# Ubo_side_v1_4.net
KiCad netlist of a schematic drawn in EAGLE
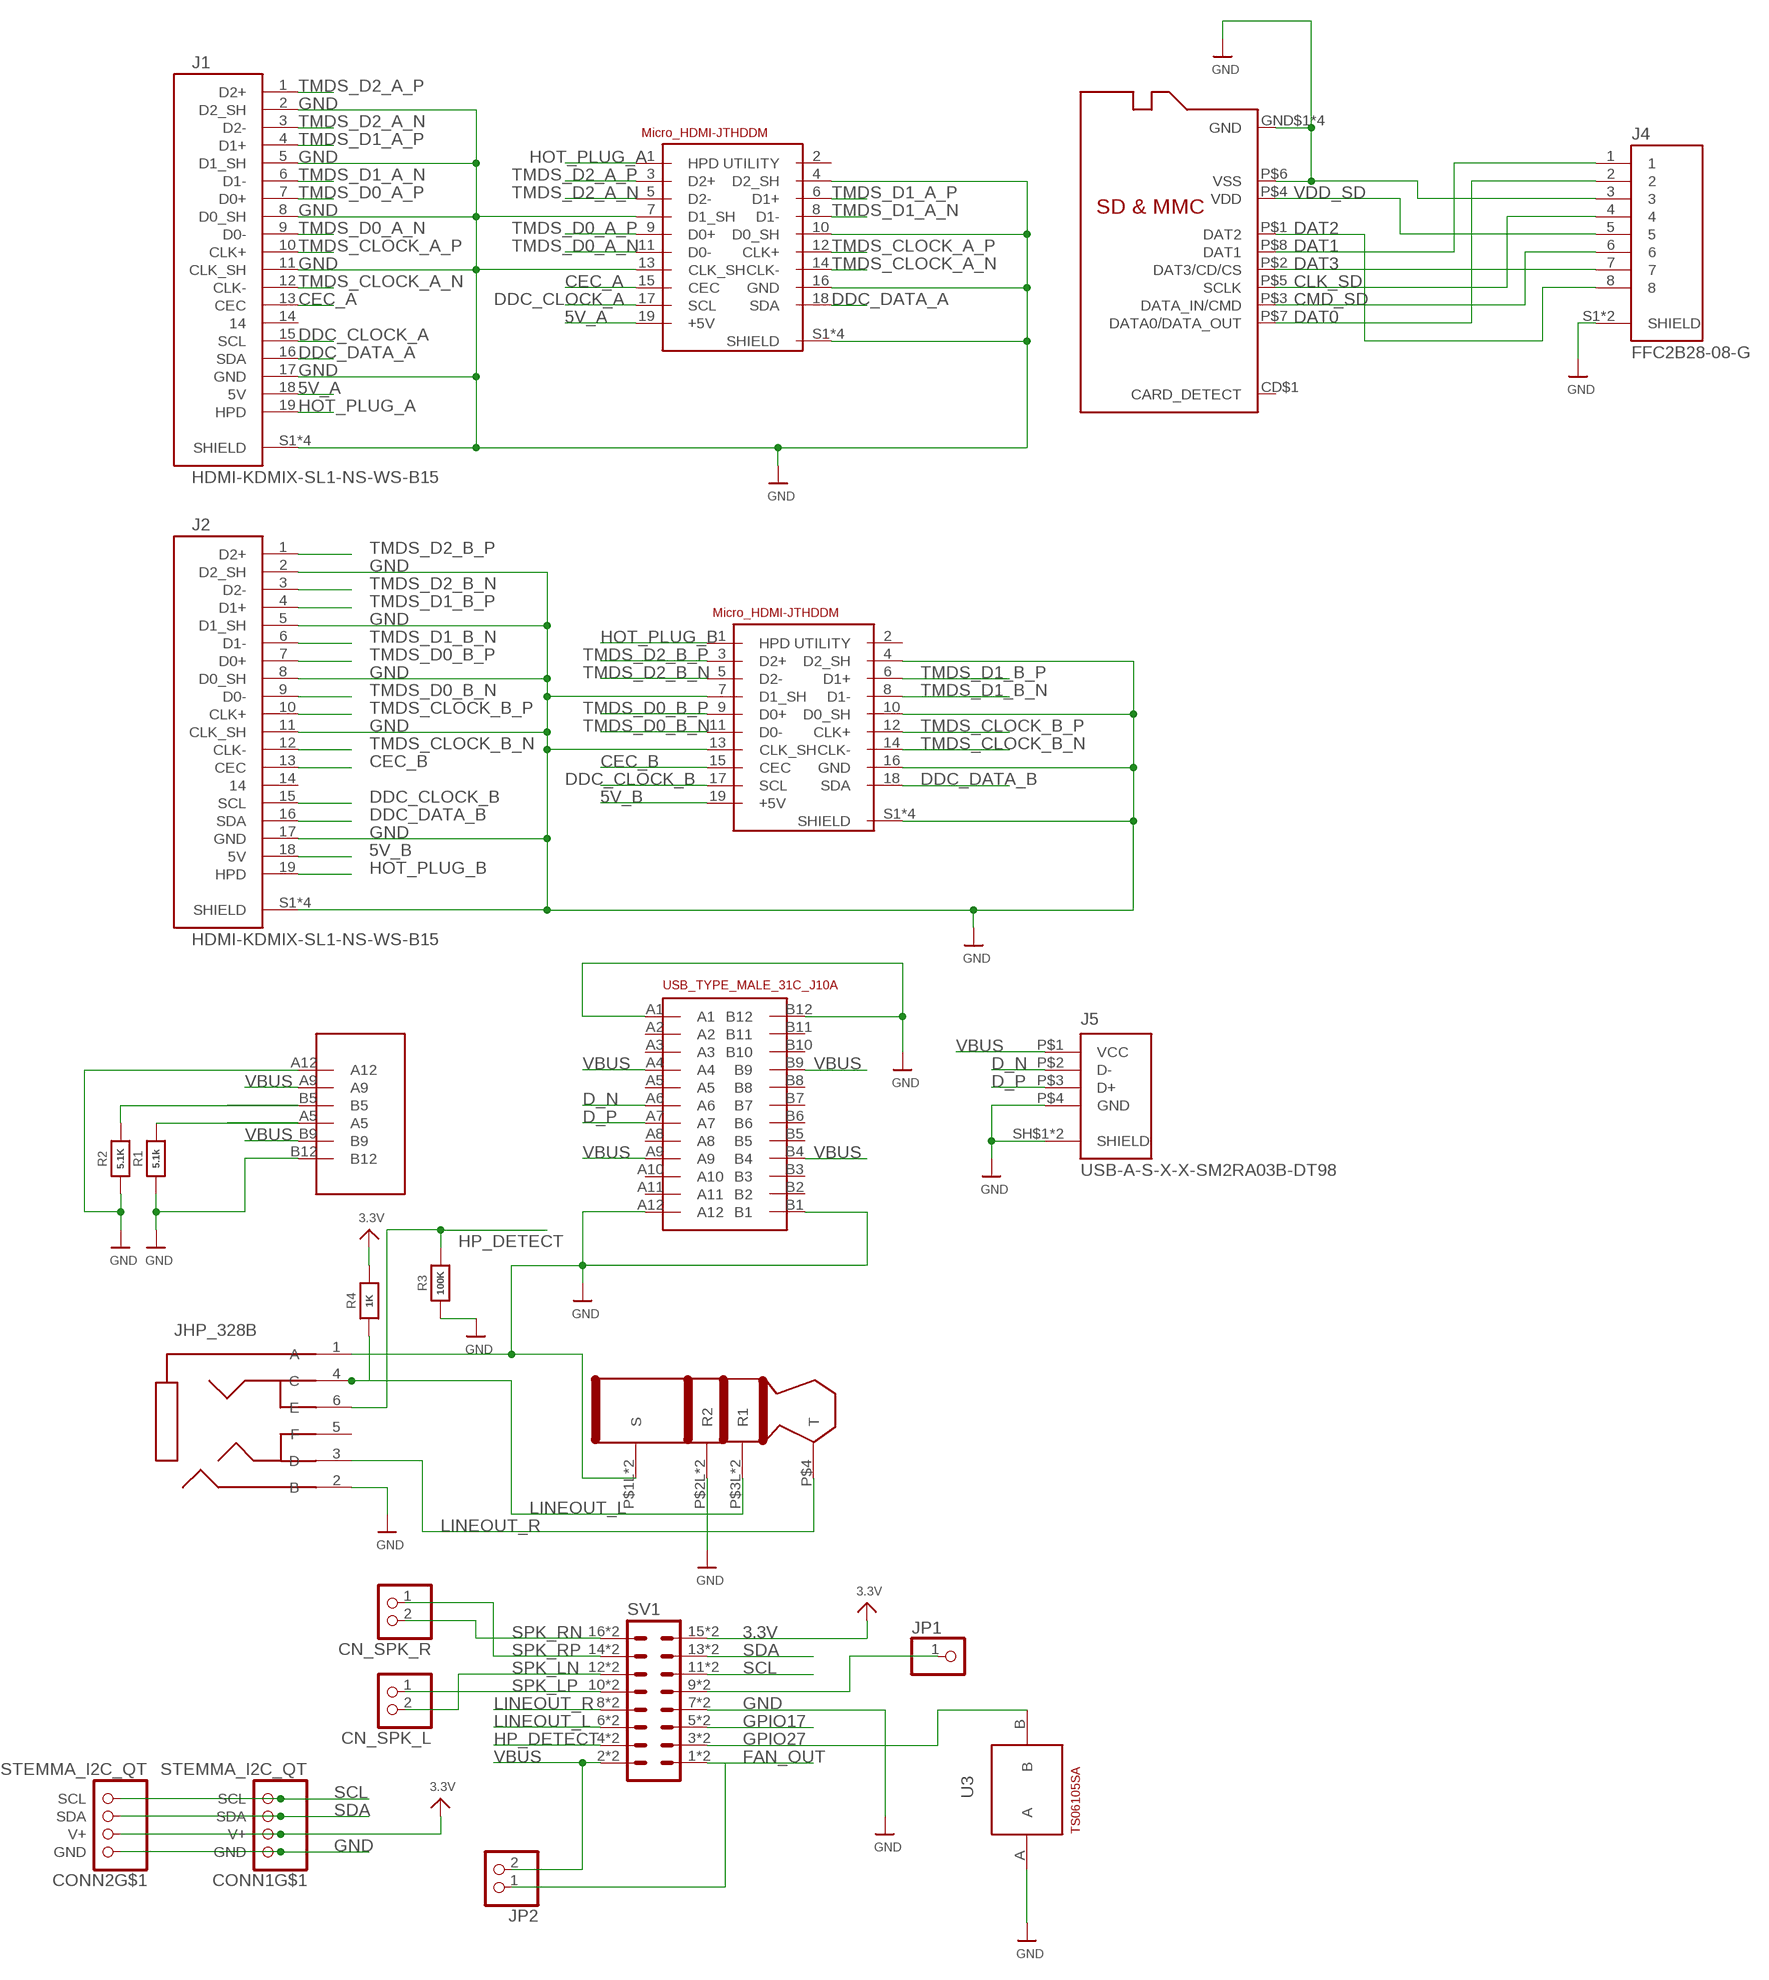
[diagram p0: schematic, sheet 1]

(export (version "E")
  (design (tool "Eeschema 10.0.6"))
  (components
    (comp (ref "AUD_CON")
      (value "AUDIO_3.5MMJACK_MALE")
      (footprint "eagle-import:AUDIO_3.5MM_JACK_MALE")
      (libsource (lib "eagle-import") (part "AUDIO_3.5MMJACK_MALE"))
    )
    (comp (ref "CN_SPK_L")
      (value "JST_2PIN-SMT")
      (footprint "eagle-import:JST-PH-2-SMT")
      (libsource (lib "eagle-import") (part "JST_2PIN-SMT"))
    )
    (comp (ref "CN_SPK_R")
      (value "JST_2PIN-SMT")
      (footprint "eagle-import:JST-PH-2-SMT")
      (libsource (lib "eagle-import") (part "JST_2PIN-SMT"))
    )
    (comp (ref "CONN1")
      (value "STEMMA_I2C_QT")
      (footprint "eagle-import:JST_SH4")
      (libsource (lib "eagle-import") (part "STEMMA_I2C_QT"))
    )
    (comp (ref "CONN2")
      (value "STEMMA_I2C_QT")
      (footprint "eagle-import:JST_SH4")
      (libsource (lib "eagle-import") (part "STEMMA_I2C_QT"))
    )
    (comp (ref "J1")
      (value "HDMI-KDMIX-SL1-NS-WS-B15")
      (footprint "eagle-import:CONN_KDMIX-SL1-NS-WS-B15")
      (fields
        (field (name "DIGI-KEY_PART_NUMBER") "2092-KDMIX-SL1-NS-WS-B15-ND")
        (field (name "MF") "Kycon")
        (field (name "MP") "KDMIX-SL1-NS-WS-B15")
      )
      (libsource (lib "eagle-import") (part "HDMI-KDMIX-SL1-NS-WS-B15"))
    )
    (comp (ref "J2")
      (value "HDMI-KDMIX-SL1-NS-WS-B15")
      (footprint "eagle-import:CONN_KDMIX-SL1-NS-WS-B15")
      (fields
        (field (name "DIGI-KEY_PART_NUMBER") "2092-KDMIX-SL1-NS-WS-B15-ND")
        (field (name "MF") "Kycon")
        (field (name "MP") "KDMIX-SL1-NS-WS-B15")
      )
      (libsource (lib "eagle-import") (part "HDMI-KDMIX-SL1-NS-WS-B15"))
    )
    (comp (ref "J4")
      (value "FFC2B28-08-G")
      (footprint "eagle-import:GCT_FFC2B28-08-G")
      (fields (field (name "MF") "Global Connector Technology"))
      (libsource (lib "eagle-import") (part "FFC2B28-08-G"))
    )
    (comp (ref "J5")
      (value "USB-A-S-X-X-SM2RA03B-DT98")
      (footprint "eagle-import:USB-A-RA03B-DT98")
      (libsource (lib "eagle-import") (part "USB-A-S-X-X-SM2RA03B-DT98"))
    )
    (comp (ref "JP1")
      (value "PINHD-1X1")
      (footprint "eagle-import:1X01")
      (libsource (lib "eagle-import") (part "PINHD-1X1"))
    )
    (comp (ref "JP2")
      (value "PINHD-1X2/90")
      (footprint "eagle-import:1X02_90")
      (libsource (lib "eagle-import") (part "PINHD-1X2/90"))
    )
    (comp (ref "MICROHDMI1")
      (value "MICRO_HDMI_JTHDDM")
      (footprint "eagle-import:MICRO_HDMI_JTHDDM")
      (fields (field (name "MF") "MTCONN ELECTRONICS CO.,LTD") (field (name "MPN") "JTHDDM_0200D1SP79"))
      (libsource (lib "eagle-import") (part "MICRO_HDMI_JTHDDM"))
    )
    (comp (ref "MICROHDMI2")
      (value "MICRO_HDMI_JTHDDM")
      (footprint "eagle-import:MICRO_HDMI_JTHDDM")
      (fields (field (name "MF") "MTCONN ELECTRONICS CO.,LTD") (field (name "MPN") "JTHDDM_0200D1SP79"))
      (libsource (lib "eagle-import") (part "MICRO_HDMI_JTHDDM"))
    )
    (comp (ref "R1")
      (value "5.1k")
      (footprint "eagle-import:_0603")
      (libsource (lib "eagle-import") (part "RESISTOR_0603"))
    )
    (comp (ref "R2")
      (value "5.1K")
      (footprint "eagle-import:_0603")
      (libsource (lib "eagle-import") (part "RESISTOR_0603"))
    )
    (comp (ref "R3")
      (value "100K")
      (footprint "eagle-import:_0603")
      (libsource (lib "eagle-import") (part "RESISTOR_0603"))
    )
    (comp (ref "R4")
      (value "1K")
      (footprint "eagle-import:_0603")
      (libsource (lib "eagle-import") (part "RESISTOR_0603"))
    )
    (comp (ref "SV1")
      (value "MA08X2-FEMALE")
      (footprint "eagle-import:MA08X2-FEMALE")
      (libsource (lib "eagle-import") (part "MA08X2-FEMALE"))
    )
    (comp (ref "U1")
      (value "AUDIO_SOCKET_JHP_328BPJ-3160")
      (footprint "eagle-import:PJ-3160")
      (libsource (lib "eagle-import") (part "AUDIO_SOCKET_JHP_328BPJ-3160"))
    )
    (comp (ref "U2")
      (value "USB-20C-F-06CD-1")
      (footprint "eagle-import:USB_20C_F_60CD")
      (libsource (lib "eagle-import") (part "USB-20C-F-06CD-1"))
    )
    (comp (ref "U3")
      (value "TS06105SA")
      (footprint "eagle-import:TS-06105SA-1")
      (libsource (lib "eagle-import") (part "TS06105SA"))
    )
    (comp (ref "U4")
      (value "MICROSDTF01-H1.8")
      (footprint "eagle-import:MICROSDTF-01-H1.8")
      (libsource (lib "eagle-import") (part "MICROSDTF01-H1.8"))
    )
    (comp (ref "USBC")
      (value "USB_TYPE_MALE_31C_J10C")
      (footprint "eagle-import:USB_TYPE_MALE_31C_J10A")
      (fields (field (name "MF") "XIAMEN JINBEILI ELECTRONICS CO.,LTD") (field (name "MPN") "USB_31C_M_J10A"))
      (libsource (lib "eagle-import") (part "USB_TYPE_MALE_31C_J10C"))
    )
  )
  (nets
    (net (code "1") (name "/5V_A") (class "Default")
      (node (ref "J1") (pin "18") (pinfunction "5V_18") (pintype "passive"))
      (node (ref "MICROHDMI1") (pin "19") (pinfunction "+5V_19") (pintype "bidirectional"))
    )
    (net (code "2") (name "/5V_B") (class "Default")
      (node (ref "J2") (pin "18") (pinfunction "5V_18") (pintype "passive"))
      (node (ref "MICROHDMI2") (pin "19") (pinfunction "+5V_19") (pintype "bidirectional"))
    )
    (net (code "3") (name "/CEC_A") (class "Default")
      (node (ref "J1") (pin "13") (pinfunction "CEC_13") (pintype "passive"))
      (node (ref "MICROHDMI1") (pin "15") (pinfunction "CEC_15") (pintype "bidirectional"))
    )
    (net (code "4") (name "/CEC_B") (class "Default")
      (node (ref "J2") (pin "13") (pinfunction "CEC_13") (pintype "passive"))
      (node (ref "MICROHDMI2") (pin "15") (pinfunction "CEC_15") (pintype "bidirectional"))
    )
    (net (code "5") (name "/CLK_SD") (class "Default")
      (node (ref "J4") (pin "4") (pinfunction "4_4") (pintype "passive"))
      (node (ref "U4") (pin "P$5") (pinfunction "SCLK_P$5") (pintype "input"))
    )
    (net (code "6") (name "/CMD_SD") (class "Default")
      (node (ref "J4") (pin "6") (pinfunction "6_6") (pintype "passive"))
      (node (ref "U4") (pin "P$3") (pinfunction "DATA_IN/CMD_P$3") (pintype "input"))
    )
    (net (code "7") (name "/DAT0") (class "Default")
      (node (ref "J4") (pin "2") (pinfunction "2_2") (pintype "passive"))
      (node (ref "U4") (pin "P$7") (pinfunction "DATA0/DATA_OUT_P$7") (pintype "output"))
    )
    (net (code "8") (name "/DAT1") (class "Default")
      (node (ref "J4") (pin "1") (pinfunction "1_1") (pintype "passive"))
      (node (ref "U4") (pin "P$8") (pinfunction "DAT1_P$8") (pintype "bidirectional"))
    )
    (net (code "9") (name "/DAT2") (class "Default")
      (node (ref "J4") (pin "8") (pinfunction "8_8") (pintype "passive"))
      (node (ref "U4") (pin "P$1") (pinfunction "DAT2_P$1") (pintype "bidirectional"))
    )
    (net (code "10") (name "/DAT3") (class "Default")
      (node (ref "J4") (pin "7") (pinfunction "7_7") (pintype "passive"))
      (node (ref "U4") (pin "P$2") (pinfunction "DAT3/CD/CS_P$2") (pintype "input"))
    )
    (net (code "11") (name "/DDC_CLOCK_A") (class "Default")
      (node (ref "J1") (pin "15") (pinfunction "SCL_15") (pintype "passive"))
      (node (ref "MICROHDMI1") (pin "17") (pinfunction "SCL_17") (pintype "bidirectional"))
    )
    (net (code "12") (name "/DDC_CLOCK_B") (class "Default")
      (node (ref "J2") (pin "15") (pinfunction "SCL_15") (pintype "passive"))
      (node (ref "MICROHDMI2") (pin "17") (pinfunction "SCL_17") (pintype "bidirectional"))
    )
    (net (code "13") (name "/DDC_DATA_A") (class "Default")
      (node (ref "J1") (pin "16") (pinfunction "SDA_16") (pintype "passive"))
      (node (ref "MICROHDMI1") (pin "18") (pinfunction "SDA_18") (pintype "bidirectional"))
    )
    (net (code "14") (name "/DDC_DATA_B") (class "Default")
      (node (ref "J2") (pin "16") (pinfunction "SDA_16") (pintype "passive"))
      (node (ref "MICROHDMI2") (pin "18") (pinfunction "SDA_18") (pintype "bidirectional"))
    )
    (net (code "15") (name "/D_N") (class "Default")
      (node (ref "J5") (pin "P$2") (pinfunction "D-_P$2") (pintype "bidirectional"))
      (node (ref "USBC") (pin "A6") (pinfunction "A6_A6") (pintype "bidirectional"))
    )
    (net (code "16") (name "/D_P") (class "Default")
      (node (ref "J5") (pin "P$3") (pinfunction "D+_P$3") (pintype "bidirectional"))
      (node (ref "USBC") (pin "A7") (pinfunction "A7_A7") (pintype "bidirectional"))
    )
    (net (code "17") (name "/FAN_OUT") (class "Default")
      (node (ref "JP2") (pin "1") (pinfunction "1_1") (pintype "passive"))
      (node (ref "SV1") (pin "1") (pinfunction "1_1") (pintype "passive"))
      (node (ref "SV1") (pin "P$1") (pinfunction "1_P$1") (pintype "passive"))
    )
    (net (code "18") (name "/GPIO17") (class "Default")
      (node (ref "SV1") (pin "5") (pinfunction "5_5") (pintype "passive"))
      (node (ref "SV1") (pin "P$5") (pinfunction "5_P$5") (pintype "passive"))
    )
    (net (code "19") (name "/GPIO27") (class "Default")
      (node (ref "SV1") (pin "3") (pinfunction "3_3") (pintype "passive"))
      (node (ref "SV1") (pin "P$3") (pinfunction "3_P$3") (pintype "passive"))
      (node (ref "U3") (pin "B") (pinfunction "B_B") (pintype "bidirectional"))
    )
    (net (code "20") (name "/HOT_PLUG_A") (class "Default")
      (node (ref "J1") (pin "19") (pinfunction "HPD_19") (pintype "passive"))
      (node (ref "MICROHDMI1") (pin "1") (pinfunction "HPD_1") (pintype "bidirectional"))
    )
    (net (code "21") (name "/HOT_PLUG_B") (class "Default")
      (node (ref "J2") (pin "19") (pinfunction "HPD_19") (pintype "passive"))
      (node (ref "MICROHDMI2") (pin "1") (pinfunction "HPD_1") (pintype "bidirectional"))
    )
    (net (code "22") (name "/HP_DETECT") (class "Default")
      (node (ref "R3") (pin "2") (pinfunction "2_2") (pintype "passive"))
      (node (ref "SV1") (pin "4") (pinfunction "4_4") (pintype "passive"))
      (node (ref "SV1") (pin "P$4") (pinfunction "4_P$4") (pintype "passive"))
      (node (ref "U1") (pin "6") (pinfunction "E_6") (pintype "bidirectional"))
    )
    (net (code "23") (name "/LINEOUT_L") (class "Default")
      (node (ref "AUD_CON") (pin "P$3L") (pinfunction "R1_P$3L") (pintype "bidirectional"))
      (node (ref "AUD_CON") (pin "P$3R") (pinfunction "R1_P$3R") (pintype "bidirectional"))
      (node (ref "R4") (pin "1") (pinfunction "1_1") (pintype "passive"))
      (node (ref "SV1") (pin "6") (pinfunction "6_6") (pintype "passive"))
      (node (ref "SV1") (pin "P$6") (pinfunction "6_P$6") (pintype "passive"))
      (node (ref "U1") (pin "4") (pinfunction "C_4") (pintype "bidirectional"))
    )
    (net (code "24") (name "/LINEOUT_R") (class "Default")
      (node (ref "AUD_CON") (pin "P$4") (pinfunction "T_P$4") (pintype "bidirectional"))
      (node (ref "SV1") (pin "8") (pinfunction "8_8") (pintype "passive"))
      (node (ref "SV1") (pin "P$8") (pinfunction "8_P$8") (pintype "passive"))
      (node (ref "U1") (pin "3") (pinfunction "D_3") (pintype "bidirectional"))
    )
    (net (code "25") (name "/SCL") (class "Default")
      (node (ref "CONN1") (pin "4") (pinfunction "SCL_4") (pintype "passive"))
      (node (ref "CONN2") (pin "4") (pinfunction "SCL_4") (pintype "passive"))
      (node (ref "SV1") (pin "11") (pinfunction "11_11") (pintype "passive"))
      (node (ref "SV1") (pin "P$11") (pinfunction "11_P$11") (pintype "passive"))
    )
    (net (code "26") (name "/SDA") (class "Default")
      (node (ref "CONN1") (pin "3") (pinfunction "SDA_3") (pintype "passive"))
      (node (ref "CONN2") (pin "3") (pinfunction "SDA_3") (pintype "passive"))
      (node (ref "SV1") (pin "13") (pinfunction "13_13") (pintype "passive"))
      (node (ref "SV1") (pin "P$13") (pinfunction "13_P$13") (pintype "passive"))
    )
    (net (code "27") (name "/SPK_LN") (class "Default")
      (node (ref "CN_SPK_L") (pin "2") (pinfunction "1_2") (pintype "passive"))
      (node (ref "SV1") (pin "12") (pinfunction "12_12") (pintype "passive"))
      (node (ref "SV1") (pin "P$12") (pinfunction "12_P$12") (pintype "passive"))
    )
    (net (code "28") (name "/SPK_LP") (class "Default")
      (node (ref "CN_SPK_L") (pin "1") (pinfunction "2_1") (pintype "passive"))
      (node (ref "SV1") (pin "10") (pinfunction "10_10") (pintype "passive"))
      (node (ref "SV1") (pin "P$10") (pinfunction "10_P$10") (pintype "passive"))
    )
    (net (code "29") (name "/SPK_RN") (class "Default")
      (node (ref "CN_SPK_R") (pin "2") (pinfunction "1_2") (pintype "passive"))
      (node (ref "SV1") (pin "16") (pinfunction "16_16") (pintype "passive"))
      (node (ref "SV1") (pin "P$16") (pinfunction "16_P$16") (pintype "passive"))
    )
    (net (code "30") (name "/SPK_RP") (class "Default")
      (node (ref "CN_SPK_R") (pin "1") (pinfunction "2_1") (pintype "passive"))
      (node (ref "SV1") (pin "14") (pinfunction "14_14") (pintype "passive"))
      (node (ref "SV1") (pin "P$14") (pinfunction "14_P$14") (pintype "passive"))
    )
    (net (code "31") (name "/TMDS_CLOCK_A_N") (class "Default")
      (node (ref "J1") (pin "12") (pinfunction "CLK-_12") (pintype "passive"))
      (node (ref "MICROHDMI1") (pin "14") (pinfunction "CLK-_14") (pintype "bidirectional"))
    )
    (net (code "32") (name "/TMDS_CLOCK_A_P") (class "Default")
      (node (ref "J1") (pin "10") (pinfunction "CLK+_10") (pintype "passive"))
      (node (ref "MICROHDMI1") (pin "12") (pinfunction "CLK+_12") (pintype "bidirectional"))
    )
    (net (code "33") (name "/TMDS_CLOCK_B_N") (class "Default")
      (node (ref "J2") (pin "12") (pinfunction "CLK-_12") (pintype "passive"))
      (node (ref "MICROHDMI2") (pin "14") (pinfunction "CLK-_14") (pintype "bidirectional"))
    )
    (net (code "34") (name "/TMDS_CLOCK_B_P") (class "Default")
      (node (ref "J2") (pin "10") (pinfunction "CLK+_10") (pintype "passive"))
      (node (ref "MICROHDMI2") (pin "12") (pinfunction "CLK+_12") (pintype "bidirectional"))
    )
    (net (code "35") (name "/TMDS_D0_A_N") (class "Default")
      (node (ref "J1") (pin "9") (pinfunction "D0-_9") (pintype "passive"))
      (node (ref "MICROHDMI1") (pin "11") (pinfunction "D0-_11") (pintype "bidirectional"))
    )
    (net (code "36") (name "/TMDS_D0_A_P") (class "Default")
      (node (ref "J1") (pin "7") (pinfunction "D0+_7") (pintype "passive"))
      (node (ref "MICROHDMI1") (pin "9") (pinfunction "D0+_9") (pintype "bidirectional"))
    )
    (net (code "37") (name "/TMDS_D0_B_N") (class "Default")
      (node (ref "J2") (pin "9") (pinfunction "D0-_9") (pintype "passive"))
      (node (ref "MICROHDMI2") (pin "11") (pinfunction "D0-_11") (pintype "bidirectional"))
    )
    (net (code "38") (name "/TMDS_D0_B_P") (class "Default")
      (node (ref "J2") (pin "7") (pinfunction "D0+_7") (pintype "passive"))
      (node (ref "MICROHDMI2") (pin "9") (pinfunction "D0+_9") (pintype "bidirectional"))
    )
    (net (code "39") (name "/TMDS_D1_A_N") (class "Default")
      (node (ref "J1") (pin "6") (pinfunction "D1-_6") (pintype "passive"))
      (node (ref "MICROHDMI1") (pin "8") (pinfunction "D1-_8") (pintype "bidirectional"))
    )
    (net (code "40") (name "/TMDS_D1_A_P") (class "Default")
      (node (ref "J1") (pin "4") (pinfunction "D1+_4") (pintype "passive"))
      (node (ref "MICROHDMI1") (pin "6") (pinfunction "D1+_6") (pintype "bidirectional"))
    )
    (net (code "41") (name "/TMDS_D1_B_N") (class "Default")
      (node (ref "J2") (pin "6") (pinfunction "D1-_6") (pintype "passive"))
      (node (ref "MICROHDMI2") (pin "8") (pinfunction "D1-_8") (pintype "bidirectional"))
    )
    (net (code "42") (name "/TMDS_D1_B_P") (class "Default")
      (node (ref "J2") (pin "4") (pinfunction "D1+_4") (pintype "passive"))
      (node (ref "MICROHDMI2") (pin "6") (pinfunction "D1+_6") (pintype "bidirectional"))
    )
    (net (code "43") (name "/TMDS_D2_A_N") (class "Default")
      (node (ref "J1") (pin "3") (pinfunction "D2-_3") (pintype "passive"))
      (node (ref "MICROHDMI1") (pin "5") (pinfunction "D2-_5") (pintype "bidirectional"))
    )
    (net (code "44") (name "/TMDS_D2_A_P") (class "Default")
      (node (ref "J1") (pin "1") (pinfunction "D2+_1") (pintype "passive"))
      (node (ref "MICROHDMI1") (pin "3") (pinfunction "D2+_3") (pintype "bidirectional"))
    )
    (net (code "45") (name "/TMDS_D2_B_N") (class "Default")
      (node (ref "J2") (pin "3") (pinfunction "D2-_3") (pintype "passive"))
      (node (ref "MICROHDMI2") (pin "5") (pinfunction "D2-_5") (pintype "bidirectional"))
    )
    (net (code "46") (name "/TMDS_D2_B_P") (class "Default")
      (node (ref "J2") (pin "1") (pinfunction "D2+_1") (pintype "passive"))
      (node (ref "MICROHDMI2") (pin "3") (pinfunction "D2+_3") (pintype "bidirectional"))
    )
    (net (code "47") (name "/VBUS") (class "Default")
      (node (ref "J5") (pin "P$1") (pinfunction "VCC_P$1") (pintype "power_in"))
      (node (ref "JP2") (pin "2") (pinfunction "2_2") (pintype "passive"))
      (node (ref "SV1") (pin "2") (pinfunction "2_2") (pintype "passive"))
      (node (ref "SV1") (pin "P$2") (pinfunction "2_P$2") (pintype "passive"))
      (node (ref "U2") (pin "A9") (pinfunction "A9_A9") (pintype "bidirectional"))
      (node (ref "U2") (pin "B9") (pinfunction "B9_B9") (pintype "bidirectional"))
      (node (ref "USBC") (pin "A4") (pinfunction "A4_A4") (pintype "bidirectional"))
      (node (ref "USBC") (pin "A9") (pinfunction "A9_A9") (pintype "bidirectional"))
      (node (ref "USBC") (pin "B4") (pinfunction "B4_B4") (pintype "bidirectional"))
      (node (ref "USBC") (pin "B9") (pinfunction "B9_B9") (pintype "bidirectional"))
    )
    (net (code "48") (name "/VDD_SD") (class "Default")
      (node (ref "J4") (pin "5") (pinfunction "5_5") (pintype "passive"))
      (node (ref "U4") (pin "P$4") (pinfunction "VDD_P$4") (pintype "power_in"))
    )
    (net (code "49") (name "3.3V") (class "Default")
      (node (ref "CONN1") (pin "2") (pinfunction "V+_2") (pintype "passive"))
      (node (ref "CONN2") (pin "2") (pinfunction "V+_2") (pintype "passive"))
      (node (ref "R4") (pin "2") (pinfunction "2_2") (pintype "passive"))
      (node (ref "SV1") (pin "15") (pinfunction "15_15") (pintype "passive"))
      (node (ref "SV1") (pin "P$15") (pinfunction "15_P$15") (pintype "passive"))
    )
    (net (code "50") (name "GND") (class "Default")
      (node (ref "AUD_CON") (pin "P$1L") (pinfunction "S_P$1L") (pintype "bidirectional"))
      (node (ref "AUD_CON") (pin "P$1R") (pinfunction "S_P$1R") (pintype "bidirectional"))
      (node (ref "AUD_CON") (pin "P$2L") (pinfunction "R2_P$2L") (pintype "bidirectional"))
      (node (ref "AUD_CON") (pin "P$2R") (pinfunction "R2_P$2R") (pintype "bidirectional"))
      (node (ref "CONN1") (pin "1") (pinfunction "GND_1") (pintype "passive"))
      (node (ref "CONN2") (pin "1") (pinfunction "GND_1") (pintype "passive"))
      (node (ref "J1") (pin "11") (pinfunction "CLK_SH_11") (pintype "passive"))
      (node (ref "J1") (pin "17") (pinfunction "GND_17") (pintype "passive"))
      (node (ref "J1") (pin "2") (pinfunction "D2_SH_2") (pintype "passive"))
      (node (ref "J1") (pin "5") (pinfunction "D1_SH_5") (pintype "passive"))
      (node (ref "J1") (pin "8") (pinfunction "D0_SH_8") (pintype "passive"))
      (node (ref "J1") (pin "S1") (pinfunction "SHIELD_S1") (pintype "passive"))
      (node (ref "J1") (pin "S2") (pinfunction "SHIELD_S2") (pintype "passive"))
      (node (ref "J1") (pin "S3") (pinfunction "SHIELD_S3") (pintype "passive"))
      (node (ref "J1") (pin "S4") (pinfunction "SHIELD_S4") (pintype "passive"))
      (node (ref "J2") (pin "11") (pinfunction "CLK_SH_11") (pintype "passive"))
      (node (ref "J2") (pin "17") (pinfunction "GND_17") (pintype "passive"))
      (node (ref "J2") (pin "2") (pinfunction "D2_SH_2") (pintype "passive"))
      (node (ref "J2") (pin "5") (pinfunction "D1_SH_5") (pintype "passive"))
      (node (ref "J2") (pin "8") (pinfunction "D0_SH_8") (pintype "passive"))
      (node (ref "J2") (pin "S1") (pinfunction "SHIELD_S1") (pintype "passive"))
      (node (ref "J2") (pin "S2") (pinfunction "SHIELD_S2") (pintype "passive"))
      (node (ref "J2") (pin "S3") (pinfunction "SHIELD_S3") (pintype "passive"))
      (node (ref "J2") (pin "S4") (pinfunction "SHIELD_S4") (pintype "passive"))
      (node (ref "J4") (pin "3") (pinfunction "3_3") (pintype "passive"))
      (node (ref "J4") (pin "S1") (pinfunction "SHIELD_S1") (pintype "passive"))
      (node (ref "J4") (pin "S2") (pinfunction "SHIELD_S2") (pintype "passive"))
      (node (ref "J5") (pin "P$4") (pinfunction "GND_P$4") (pintype "power_in"))
      (node (ref "J5") (pin "SH$1") (pinfunction "SHIELD_SH$1") (pintype "passive"))
      (node (ref "J5") (pin "SH$2") (pinfunction "SHIELD_SH$2") (pintype "passive"))
      (node (ref "MICROHDMI1") (pin "10") (pinfunction "D0_SH_10") (pintype "bidirectional"))
      (node (ref "MICROHDMI1") (pin "13") (pinfunction "CLK_SH_13") (pintype "bidirectional"))
      (node (ref "MICROHDMI1") (pin "16") (pinfunction "GND_16") (pintype "bidirectional"))
      (node (ref "MICROHDMI1") (pin "4") (pinfunction "D2_SH_4") (pintype "bidirectional"))
      (node (ref "MICROHDMI1") (pin "7") (pinfunction "D1_SH_7") (pintype "bidirectional"))
      (node (ref "MICROHDMI1") (pin "S1") (pinfunction "SHIELD_S1") (pintype "bidirectional"))
      (node (ref "MICROHDMI1") (pin "S2") (pinfunction "SHIELD_S2") (pintype "bidirectional"))
      (node (ref "MICROHDMI1") (pin "S3") (pinfunction "SHIELD_S3") (pintype "bidirectional"))
      (node (ref "MICROHDMI1") (pin "S4") (pinfunction "SHIELD_S4") (pintype "bidirectional"))
      (node (ref "MICROHDMI2") (pin "10") (pinfunction "D0_SH_10") (pintype "bidirectional"))
      (node (ref "MICROHDMI2") (pin "13") (pinfunction "CLK_SH_13") (pintype "bidirectional"))
      (node (ref "MICROHDMI2") (pin "16") (pinfunction "GND_16") (pintype "bidirectional"))
      (node (ref "MICROHDMI2") (pin "4") (pinfunction "D2_SH_4") (pintype "bidirectional"))
      (node (ref "MICROHDMI2") (pin "7") (pinfunction "D1_SH_7") (pintype "bidirectional"))
      (node (ref "MICROHDMI2") (pin "S1") (pinfunction "SHIELD_S1") (pintype "bidirectional"))
      (node (ref "MICROHDMI2") (pin "S2") (pinfunction "SHIELD_S2") (pintype "bidirectional"))
      (node (ref "MICROHDMI2") (pin "S3") (pinfunction "SHIELD_S3") (pintype "bidirectional"))
      (node (ref "MICROHDMI2") (pin "S4") (pinfunction "SHIELD_S4") (pintype "bidirectional"))
      (node (ref "R1") (pin "1") (pinfunction "1_1") (pintype "passive"))
      (node (ref "R2") (pin "1") (pinfunction "1_1") (pintype "passive"))
      (node (ref "R3") (pin "1") (pinfunction "1_1") (pintype "passive"))
      (node (ref "SV1") (pin "7") (pinfunction "7_7") (pintype "passive"))
      (node (ref "SV1") (pin "P$7") (pinfunction "7_P$7") (pintype "passive"))
      (node (ref "U1") (pin "1") (pinfunction "A_1") (pintype "bidirectional"))
      (node (ref "U1") (pin "2") (pinfunction "B_2") (pintype "bidirectional"))
      (node (ref "U2") (pin "A12") (pinfunction "A12_A12") (pintype "bidirectional"))
      (node (ref "U2") (pin "B12") (pinfunction "B12_B12") (pintype "bidirectional"))
      (node (ref "U3") (pin "A") (pinfunction "A_A") (pintype "bidirectional"))
      (node (ref "U4") (pin "GND$1") (pinfunction "GND_GND$1") (pintype "power_in"))
      (node (ref "U4") (pin "GND$2") (pinfunction "GND_GND$2") (pintype "power_in"))
      (node (ref "U4") (pin "GND$3") (pinfunction "GND_GND$3") (pintype "power_in"))
      (node (ref "U4") (pin "GND$4") (pinfunction "GND_GND$4") (pintype "power_in"))
      (node (ref "U4") (pin "P$6") (pinfunction "VSS_P$6") (pintype "power_in"))
      (node (ref "USBC") (pin "A1") (pinfunction "A1_A1") (pintype "bidirectional"))
      (node (ref "USBC") (pin "A12") (pinfunction "A12_A12") (pintype "bidirectional"))
      (node (ref "USBC") (pin "B1") (pinfunction "B1_B1") (pintype "bidirectional"))
      (node (ref "USBC") (pin "B12") (pinfunction "B12_B12") (pintype "bidirectional"))
    )
    (net (code "51") (name "Net-(JP1-Pad1)") (class "Default")
      (node (ref "JP1") (pin "1") (pinfunction "1_1") (pintype "passive"))
      (node (ref "SV1") (pin "9") (pinfunction "9_9") (pintype "passive"))
      (node (ref "SV1") (pin "P$9") (pinfunction "9_P$9") (pintype "passive"))
    )
    (net (code "52") (name "Net-(R1-Pad2)") (class "Default")
      (node (ref "R1") (pin "2") (pinfunction "2_2") (pintype "passive"))
      (node (ref "U2") (pin "A5") (pinfunction "A5_A5") (pintype "bidirectional"))
    )
    (net (code "53") (name "Net-(R2-Pad2)") (class "Default")
      (node (ref "R2") (pin "2") (pinfunction "2_2") (pintype "passive"))
      (node (ref "U2") (pin "B5") (pinfunction "B5_B5") (pintype "bidirectional"))
    )
    (net (code "54") (name "unconnected-(J1-Pad14)") (class "Default")
      (node (ref "J1") (pin "14") (pinfunction "14_14") (pintype "passive"))
    )
    (net (code "55") (name "unconnected-(J2-Pad14)") (class "Default")
      (node (ref "J2") (pin "14") (pinfunction "14_14") (pintype "passive"))
    )
    (net (code "56") (name "unconnected-(MICROHDMI1-UTILITY-Pad2)") (class "Default")
      (node (ref "MICROHDMI1") (pin "2") (pinfunction "UTILITY_2") (pintype "bidirectional"))
    )
    (net (code "57") (name "unconnected-(MICROHDMI2-UTILITY-Pad2)") (class "Default")
      (node (ref "MICROHDMI2") (pin "2") (pinfunction "UTILITY_2") (pintype "bidirectional"))
    )
    (net (code "58") (name "unconnected-(U1-F-Pad5)") (class "Default")
      (node (ref "U1") (pin "5") (pinfunction "F_5") (pintype "bidirectional"))
    )
    (net (code "59") (name "unconnected-(U4-CARD_DETECT-PadCD$1)") (class "Default")
      (node (ref "U4") (pin "CD$1") (pinfunction "CARD_DETECT_CD$1") (pintype "passive"))
    )
    (net (code "60") (name "unconnected-(USBC-PadA2)") (class "Default")
      (node (ref "USBC") (pin "A2") (pinfunction "A2_A2") (pintype "bidirectional"))
    )
    (net (code "61") (name "unconnected-(USBC-PadA3)") (class "Default")
      (node (ref "USBC") (pin "A3") (pinfunction "A3_A3") (pintype "bidirectional"))
    )
    (net (code "62") (name "unconnected-(USBC-PadA5)") (class "Default")
      (node (ref "USBC") (pin "A5") (pinfunction "A5_A5") (pintype "bidirectional"))
    )
    (net (code "63") (name "unconnected-(USBC-PadA8)") (class "Default")
      (node (ref "USBC") (pin "A8") (pinfunction "A8_A8") (pintype "bidirectional"))
    )
    (net (code "64") (name "unconnected-(USBC-PadA10)") (class "Default")
      (node (ref "USBC") (pin "A10") (pinfunction "A10_A10") (pintype "bidirectional"))
    )
    (net (code "65") (name "unconnected-(USBC-PadA11)") (class "Default")
      (node (ref "USBC") (pin "A11") (pinfunction "A11_A11") (pintype "bidirectional"))
    )
    (net (code "66") (name "unconnected-(USBC-PadB2)") (class "Default")
      (node (ref "USBC") (pin "B2") (pinfunction "B2_B2") (pintype "bidirectional"))
    )
    (net (code "67") (name "unconnected-(USBC-PadB3)") (class "Default")
      (node (ref "USBC") (pin "B3") (pinfunction "B3_B3") (pintype "bidirectional"))
    )
    (net (code "68") (name "unconnected-(USBC-PadB5)") (class "Default")
      (node (ref "USBC") (pin "B5") (pinfunction "B5_B5") (pintype "bidirectional"))
    )
    (net (code "69") (name "unconnected-(USBC-PadB6)") (class "Default")
      (node (ref "USBC") (pin "B6") (pinfunction "B6_B6") (pintype "bidirectional"))
    )
    (net (code "70") (name "unconnected-(USBC-PadB7)") (class "Default")
      (node (ref "USBC") (pin "B7") (pinfunction "B7_B7") (pintype "bidirectional"))
    )
    (net (code "71") (name "unconnected-(USBC-PadB8)") (class "Default")
      (node (ref "USBC") (pin "B8") (pinfunction "B8_B8") (pintype "bidirectional"))
    )
    (net (code "72") (name "unconnected-(USBC-PadB10)") (class "Default")
      (node (ref "USBC") (pin "B10") (pinfunction "B10_B10") (pintype "bidirectional"))
    )
    (net (code "73") (name "unconnected-(USBC-PadB11)") (class "Default")
      (node (ref "USBC") (pin "B11") (pinfunction "B11_B11") (pintype "bidirectional"))
    )
  )
)
